# Classic-Narrow-5V-SIDE-USB-JMPR.net
KiCad netlist of a schematic drawn in EAGLE
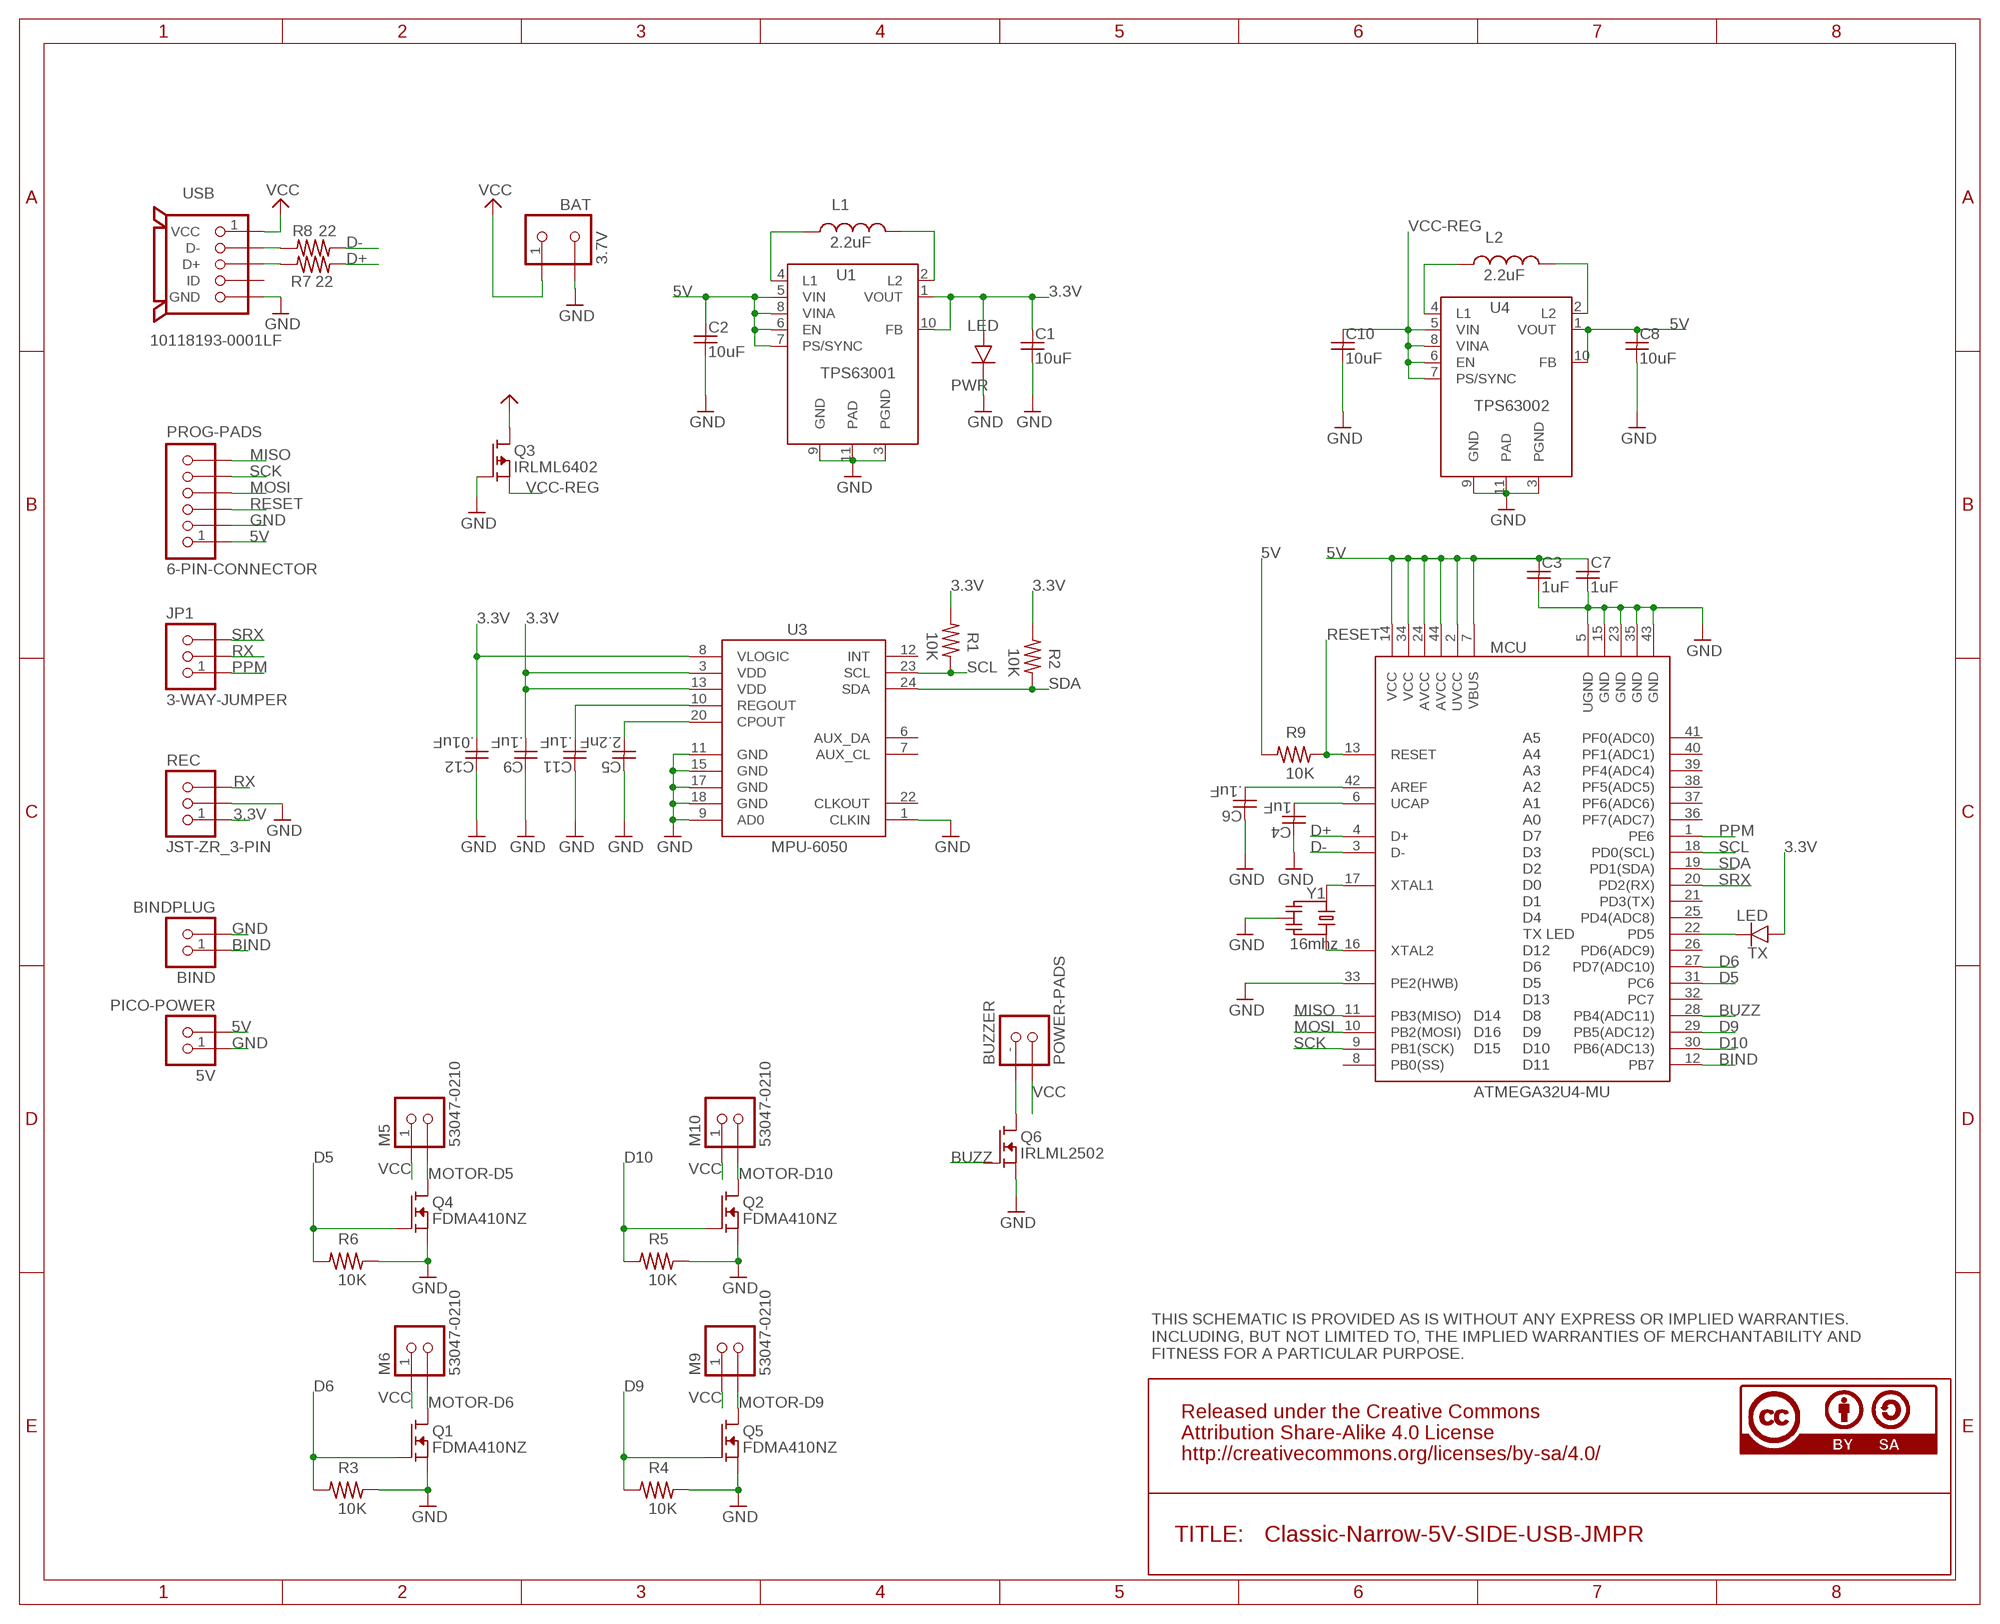
[diagram p0: schematic, sheet 1]

(export (version "E")
  (design (tool "Eeschema 10.0.6"))
  (components
    (comp (ref "5V")
      (value "PICO-POWER")
      (footprint "eagle-import:PICO_1.25_.5MM")
      (fields (field (name "MF") "Molex") (field (name "MPN") "53047-0210"))
      (libsource (lib "eagle-import") (part "PICO-POWER"))
    )
    (comp (ref "BAT")
      (value "3.7V")
      (footprint "eagle-import:S2B-PH-K-S")
      (fields (field (name "MF") "JST") (field (name "MPN") "S2B-PH-K-S"))
      (libsource (lib "eagle-import") (part "JST-PH-BAT"))
    )
    (comp (ref "BIND")
      (value "BINDPLUG")
      (footprint "eagle-import:1.27MM-PINHEADX2")
      (fields (field (name "MF") "Sullins") (field (name "MPN") "GRPB021VWVN-RC (JUMPER IS M50-1930005)"))
      (libsource (lib "eagle-import") (part "1.27MM-PINHEADX2"))
    )
    (comp (ref "BUZZER")
      (value "POWER-PADS")
      (footprint "eagle-import:POW-PADS")
      (libsource (lib "eagle-import") (part "POWER-PADS"))
    )
    (comp (ref "C1")
      (value "10uF")
      (footprint "eagle-import:YUDEN-CAP-0805")
      (fields (field (name "MF") "Taiyo Yuden") (field (name "MPN") "JMK212AB7106KG-T"))
      (libsource (lib "eagle-import") (part "CAPACITOR10UF"))
    )
    (comp (ref "C2")
      (value "10uF")
      (footprint "eagle-import:YUDEN-CAP-0805")
      (fields (field (name "MF") "Taiyo Yuden") (field (name "MPN") "JMK212AB7106KG-T"))
      (libsource (lib "eagle-import") (part "CAPACITOR10UF"))
    )
    (comp (ref "C3")
      (value "1uF")
      (footprint "eagle-import:MUR-CAP-0603")
      (fields (field (name "MF") "Murata") (field (name "MPN") "GRM188R71C105KA12D"))
      (libsource (lib "eagle-import") (part "CAPACITOR1UF"))
    )
    (comp (ref "C4")
      (value "1uF")
      (footprint "eagle-import:MUR-CAP-0603")
      (fields (field (name "MF") "Murata") (field (name "MPN") "GRM188R71C105KA12D"))
      (libsource (lib "eagle-import") (part "CAPACITOR1UF"))
    )
    (comp (ref "C5")
      (value "2.2nF")
      (footprint "eagle-import:MUR-CAP-0603")
      (fields (field (name "MF") "Murata") (field (name "MPN") "GRM188R71C222KA01D"))
      (libsource (lib "eagle-import") (part "CAPACITOR2.2NF"))
    )
    (comp (ref "C6")
      (value ".1uF")
      (footprint "eagle-import:MUR-CAP-0603")
      (fields (field (name "MF") "Murata") (field (name "MPN") "GRM188R71C104KA01D"))
      (libsource (lib "eagle-import") (part "CAPACITOR.1UF"))
    )
    (comp (ref "C7")
      (value "1uF")
      (footprint "eagle-import:MUR-CAP-0603")
      (fields (field (name "MF") "Murata") (field (name "MPN") "GRM188R71C105KA12D"))
      (libsource (lib "eagle-import") (part "CAPACITOR1UF"))
    )
    (comp (ref "C8")
      (value "10uF")
      (footprint "eagle-import:YUDEN-CAP-0805")
      (fields (field (name "MF") "Taiyo Yuden") (field (name "MPN") "JMK212AB7106KG-T"))
      (libsource (lib "eagle-import") (part "CAPACITOR10UF"))
    )
    (comp (ref "C9")
      (value ".1uF")
      (footprint "eagle-import:MUR-CAP-0603")
      (fields (field (name "MF") "Murata") (field (name "MPN") "GRM188R71C104KA01D"))
      (libsource (lib "eagle-import") (part "CAPACITOR.1UF"))
    )
    (comp (ref "C10")
      (value "10uF")
      (footprint "eagle-import:YUDEN-CAP-0805")
      (fields (field (name "MF") "Taiyo Yuden") (field (name "MPN") "JMK212AB7106KG-T"))
      (libsource (lib "eagle-import") (part "CAPACITOR10UF"))
    )
    (comp (ref "C11")
      (value ".1uF")
      (footprint "eagle-import:MUR-CAP-0603")
      (fields (field (name "MF") "Murata") (field (name "MPN") "GRM188R71C104KA01D"))
      (libsource (lib "eagle-import") (part "CAPACITOR.1UF"))
    )
    (comp (ref "C12")
      (value ".01uF")
      (footprint "eagle-import:MUR-CAP-0603")
      (fields (field (name "MF") "Murata") (field (name "MPN") "GRM188R71C103KA01D"))
      (libsource (lib "eagle-import") (part "CAPACITOR.01UF"))
    )
    (comp (ref "JP1")
      (value "3-WAY-JUMPER")
      (footprint "eagle-import:3-WAY-JUMPER")
      (libsource (lib "eagle-import") (part "3-WAY-JUMPER"))
    )
    (comp (ref "L1")
      (value "2.2uF")
      (footprint "eagle-import:NR301X")
      (fields (field (name "MF") "Taiyo Yuden") (field (name "MPN") "NR3015T2R2M"))
      (libsource (lib "eagle-import") (part "NR301X"))
    )
    (comp (ref "L2")
      (value "2.2uF")
      (footprint "eagle-import:NR301X")
      (fields (field (name "MF") "Taiyo Yuden") (field (name "MPN") "NR3015T2R2M"))
      (libsource (lib "eagle-import") (part "NR301X"))
    )
    (comp (ref "M5")
      (value "53047-0210")
      (footprint "eagle-import:PICO-53047-02")
      (fields (field (name "MF") "MOLEX"))
      (libsource (lib "eagle-import") (part "PICO-1.25-MOTOR"))
    )
    (comp (ref "M6")
      (value "53047-0210")
      (footprint "eagle-import:PICO-53047-02")
      (fields (field (name "MF") "MOLEX"))
      (libsource (lib "eagle-import") (part "PICO-1.25-MOTOR"))
    )
    (comp (ref "M9")
      (value "53047-0210")
      (footprint "eagle-import:PICO-53047-02")
      (fields (field (name "MF") "MOLEX"))
      (libsource (lib "eagle-import") (part "PICO-1.25-MOTOR"))
    )
    (comp (ref "M10")
      (value "53047-0210")
      (footprint "eagle-import:PICO-53047-02")
      (fields (field (name "MF") "MOLEX"))
      (libsource (lib "eagle-import") (part "PICO-1.25-MOTOR"))
    )
    (comp (ref "MCU")
      (value "ATMEGA32U4-MU")
      (footprint "eagle-import:QFN44-7X7")
      (fields (field (name "MF") "Atmel") (field (name "MPN") "Atmega32U4-MU"))
      (libsource (lib "eagle-import") (part "ATMEGA32U4-MU"))
    )
    (comp (ref "PROG-PADS")
      (value "6-PIN-CONNECTOR")
      (footprint "eagle-import:B6B-ZR")
      (fields (field (name "MF") "JST") (field (name "MPN") "B6B-ZR(LF)(SN)"))
      (libsource (lib "eagle-import") (part "6-PIN-CONNECTOR"))
    )
    (comp (ref "PWR")
      (value "LED")
      (footprint "eagle-import:SMD-CHIP-LED-0805")
      (fields (field (name "MF") "Kingbright") (field (name "MPN") "APHCM2012QBC/D-F01"))
      (libsource (lib "eagle-import") (part "SMD-CHIP-LED-0805"))
    )
    (comp (ref "Q1")
      (value "FDMA410NZ")
      (footprint "eagle-import:MICROFET-2X2")
      (fields (field (name "MF") "Fairchild"))
      (libsource (lib "eagle-import") (part "FDMA410NZ"))
    )
    (comp (ref "Q2")
      (value "FDMA410NZ")
      (footprint "eagle-import:MICROFET-2X2")
      (fields (field (name "MF") "Fairchild"))
      (libsource (lib "eagle-import") (part "FDMA410NZ"))
    )
    (comp (ref "Q3")
      (value "IRLML6402")
      (footprint "eagle-import:SOT-23")
      (fields (field (name "MF") "IR"))
      (libsource (lib "eagle-import") (part "MOSFET-P"))
    )
    (comp (ref "Q4")
      (value "FDMA410NZ")
      (footprint "eagle-import:MICROFET-2X2")
      (fields (field (name "MF") "Fairchild"))
      (libsource (lib "eagle-import") (part "FDMA410NZ"))
    )
    (comp (ref "Q5")
      (value "FDMA410NZ")
      (footprint "eagle-import:MICROFET-2X2")
      (fields (field (name "MF") "Fairchild"))
      (libsource (lib "eagle-import") (part "FDMA410NZ"))
    )
    (comp (ref "Q6")
      (value "IRLML2502")
      (footprint "eagle-import:SOT-23")
      (fields (field (name "MF") "IR"))
      (libsource (lib "eagle-import") (part "MOSFET-N2502"))
    )
    (comp (ref "R1")
      (value "10K")
      (footprint "eagle-import:VISH-RES-0603")
      (fields (field (name "MF") "Vishay") (field (name "MPN") "CRCW060310K0FKEAHP"))
      (libsource (lib "eagle-import") (part "RESISTOR10K"))
    )
    (comp (ref "R2")
      (value "10K")
      (footprint "eagle-import:VISH-RES-0603")
      (fields (field (name "MF") "Vishay") (field (name "MPN") "CRCW060310K0FKEAHP"))
      (libsource (lib "eagle-import") (part "RESISTOR10K"))
    )
    (comp (ref "R3")
      (value "10K")
      (footprint "eagle-import:VISH-RES-0603")
      (fields (field (name "MF") "Vishay") (field (name "MPN") "CRCW060310K0FKEAHP"))
      (libsource (lib "eagle-import") (part "RESISTOR10K"))
    )
    (comp (ref "R4")
      (value "10K")
      (footprint "eagle-import:VISH-RES-0603")
      (fields (field (name "MF") "Vishay") (field (name "MPN") "CRCW060310K0FKEAHP"))
      (libsource (lib "eagle-import") (part "RESISTOR10K"))
    )
    (comp (ref "R5")
      (value "10K")
      (footprint "eagle-import:VISH-RES-0603")
      (fields (field (name "MF") "Vishay") (field (name "MPN") "CRCW060310K0FKEAHP"))
      (libsource (lib "eagle-import") (part "RESISTOR10K"))
    )
    (comp (ref "R6")
      (value "10K")
      (footprint "eagle-import:VISH-RES-0603")
      (fields (field (name "MF") "Vishay") (field (name "MPN") "CRCW060310K0FKEAHP"))
      (libsource (lib "eagle-import") (part "RESISTOR10K"))
    )
    (comp (ref "R7")
      (value "22")
      (footprint "eagle-import:VISH-RES-0603")
      (fields (field (name "MF") "Vishay") (field (name "MPN") "CRCW060322R0FKEAHP"))
      (libsource (lib "eagle-import") (part "RESISTOR22"))
    )
    (comp (ref "R8")
      (value "22")
      (footprint "eagle-import:VISH-RES-0603")
      (fields (field (name "MF") "Vishay") (field (name "MPN") "CRCW060322R0FKEAHP"))
      (libsource (lib "eagle-import") (part "RESISTOR22"))
    )
    (comp (ref "R9")
      (value "10K")
      (footprint "eagle-import:VISH-RES-0603")
      (fields (field (name "MF") "Vishay") (field (name "MPN") "CRCW060310K0FKEAHP"))
      (libsource (lib "eagle-import") (part "RESISTOR10K"))
    )
    (comp (ref "REC")
      (value "JST-ZR_3-PIN")
      (footprint "eagle-import:S3B-ZR")
      (fields (field (name "MF") "JST") (field (name "MPN") "S3B-ZR"))
      (libsource (lib "eagle-import") (part "JST-ZR_3-PIN"))
    )
    (comp (ref "TX")
      (value "LED")
      (footprint "eagle-import:SMD-CHIP-LED-0805")
      (fields (field (name "MF") "Kingbright") (field (name "MPN") "APHCM2012QBC/D-F01"))
      (libsource (lib "eagle-import") (part "SMD-CHIP-LED-0805"))
    )
    (comp (ref "U1")
      (value "TPS63001")
      (footprint "eagle-import:VSON-N10")
      (fields (field (name "MF") "TI") (field (name "MPN") "TPS63001DRCR"))
      (libsource (lib "eagle-import") (part "TPS630XX-TPS63001"))
    )
    (comp (ref "U3")
      (value "MPU-6050")
      (footprint "eagle-import:QFN24-4X4")
      (fields (field (name "MF") "Invensense"))
      (libsource (lib "eagle-import") (part "MPU-6050"))
    )
    (comp (ref "U4")
      (value "TPS63002")
      (footprint "eagle-import:VSON-N10")
      (fields (field (name "MF") "TI") (field (name "MPN") "TPS63002DRCR"))
      (libsource (lib "eagle-import") (part "TPS630XX-TPS63002"))
    )
    (comp (ref "USB")
      (value "10118193-0001LF")
      (footprint "eagle-import:10118193-0001LF")
      (fields (field (name "MF") "FCI"))
      (libsource (lib "eagle-import") (part "USB-MICRO-B-FCI"))
    )
    (comp (ref "Y1")
      (value "16mhz")
      (footprint "eagle-import:RESONATOR_16")
      (fields (field (name "MF") "Murata") (field (name "MPN") "CSTCE16M0V53-R0"))
      (libsource (lib "eagle-import") (part "RESONATOR16MHZ"))
    )
  )
  (nets
    (net (code "1") (name "/3.3V") (class "Default")
      (node (ref "C1") (pin "1") (pinfunction "1_1") (pintype "passive"))
      (node (ref "C12") (pin "2") (pinfunction "2_2") (pintype "passive"))
      (node (ref "C9") (pin "2") (pinfunction "2_2") (pintype "passive"))
      (node (ref "PWR") (pin "A") (pinfunction "A_A") (pintype "passive"))
      (node (ref "R1") (pin "2") (pinfunction "2_2") (pintype "passive"))
      (node (ref "R2") (pin "2") (pinfunction "2_2") (pintype "passive"))
      (node (ref "REC") (pin "1") (pinfunction "1_1") (pintype "bidirectional"))
      (node (ref "TX") (pin "A") (pinfunction "A_A") (pintype "passive"))
      (node (ref "U1") (pin "1") (pinfunction "VOUT_1") (pintype "bidirectional"))
      (node (ref "U1") (pin "10") (pinfunction "FB_10") (pintype "bidirectional"))
      (node (ref "U3") (pin "13") (pinfunction "VDD_13") (pintype "bidirectional"))
      (node (ref "U3") (pin "3") (pinfunction "VDD_3") (pintype "bidirectional"))
      (node (ref "U3") (pin "8") (pinfunction "VLOGIC_8") (pintype "bidirectional"))
    )
    (net (code "2") (name "/5V") (class "Default")
      (node (ref "5V") (pin "2") (pinfunction "2_2") (pintype "passive"))
      (node (ref "C2") (pin "1") (pinfunction "1_1") (pintype "passive"))
      (node (ref "C3") (pin "1") (pinfunction "1_1") (pintype "passive"))
      (node (ref "C7") (pin "1") (pinfunction "1_1") (pintype "passive"))
      (node (ref "C8") (pin "1") (pinfunction "1_1") (pintype "passive"))
      (node (ref "MCU") (pin "14") (pinfunction "VCC_14") (pintype "bidirectional"))
      (node (ref "MCU") (pin "2") (pinfunction "UVCC_2") (pintype "bidirectional"))
      (node (ref "MCU") (pin "24") (pinfunction "AVCC_24") (pintype "bidirectional"))
      (node (ref "MCU") (pin "34") (pinfunction "VCC_34") (pintype "bidirectional"))
      (node (ref "MCU") (pin "44") (pinfunction "AVCC_44") (pintype "bidirectional"))
      (node (ref "MCU") (pin "7") (pinfunction "VBUS_7") (pintype "bidirectional"))
      (node (ref "PROG-PADS") (pin "1") (pinfunction "1_1") (pintype "bidirectional"))
      (node (ref "R9") (pin "2") (pinfunction "2_2") (pintype "passive"))
      (node (ref "U1") (pin "5") (pinfunction "VIN_5") (pintype "bidirectional"))
      (node (ref "U1") (pin "6") (pinfunction "EN_6") (pintype "bidirectional"))
      (node (ref "U1") (pin "7") (pinfunction "PS/SYNC_7") (pintype "bidirectional"))
      (node (ref "U1") (pin "8") (pinfunction "VINA_8") (pintype "bidirectional"))
      (node (ref "U4") (pin "1") (pinfunction "VOUT_1") (pintype "bidirectional"))
      (node (ref "U4") (pin "10") (pinfunction "FB_10") (pintype "bidirectional"))
    )
    (net (code "3") (name "/BIND") (class "Default")
      (node (ref "BIND") (pin "1") (pinfunction "1_1") (pintype "passive"))
      (node (ref "MCU") (pin "12") (pinfunction "PB7_12") (pintype "bidirectional"))
    )
    (net (code "4") (name "/BUZZ") (class "Default")
      (node (ref "MCU") (pin "28") (pinfunction "PB4(ADC11)_28") (pintype "bidirectional"))
      (node (ref "Q6") (pin "1") (pinfunction "G_1") (pintype "bidirectional"))
    )
    (net (code "5") (name "/D+") (class "Default")
      (node (ref "MCU") (pin "4") (pinfunction "D+_4") (pintype "bidirectional"))
      (node (ref "R7") (pin "1") (pinfunction "1_1") (pintype "passive"))
    )
    (net (code "6") (name "/D-") (class "Default")
      (node (ref "MCU") (pin "3") (pinfunction "D-_3") (pintype "bidirectional"))
      (node (ref "R8") (pin "1") (pinfunction "1_1") (pintype "passive"))
    )
    (net (code "7") (name "/D5") (class "Default")
      (node (ref "MCU") (pin "31") (pinfunction "PC6_31") (pintype "bidirectional"))
      (node (ref "Q4") (pin "G") (pinfunction "G_G") (pintype "bidirectional"))
      (node (ref "R6") (pin "2") (pinfunction "2_2") (pintype "passive"))
    )
    (net (code "8") (name "/D6") (class "Default")
      (node (ref "MCU") (pin "27") (pinfunction "PD7(ADC10)_27") (pintype "bidirectional"))
      (node (ref "Q1") (pin "G") (pinfunction "G_G") (pintype "bidirectional"))
      (node (ref "R3") (pin "2") (pinfunction "2_2") (pintype "passive"))
    )
    (net (code "9") (name "/D9") (class "Default")
      (node (ref "MCU") (pin "29") (pinfunction "PB5(ADC12)_29") (pintype "bidirectional"))
      (node (ref "Q5") (pin "G") (pinfunction "G_G") (pintype "bidirectional"))
      (node (ref "R4") (pin "2") (pinfunction "2_2") (pintype "passive"))
    )
    (net (code "10") (name "/D10") (class "Default")
      (node (ref "MCU") (pin "30") (pinfunction "PB6(ADC13)_30") (pintype "bidirectional"))
      (node (ref "Q2") (pin "G") (pinfunction "G_G") (pintype "bidirectional"))
      (node (ref "R5") (pin "2") (pinfunction "2_2") (pintype "passive"))
    )
    (net (code "11") (name "/MISO") (class "Default")
      (node (ref "MCU") (pin "11") (pinfunction "PB3(MISO)_11") (pintype "bidirectional"))
      (node (ref "PROG-PADS") (pin "6") (pinfunction "6_6") (pintype "bidirectional"))
    )
    (net (code "12") (name "/MOSI") (class "Default")
      (node (ref "MCU") (pin "10") (pinfunction "PB2(MOSI)_10") (pintype "bidirectional"))
      (node (ref "PROG-PADS") (pin "4") (pinfunction "4_4") (pintype "bidirectional"))
    )
    (net (code "13") (name "/MOTOR-D5") (class "Default")
      (node (ref "M5") (pin "2") (pinfunction "2_2") (pintype "passive"))
      (node (ref "Q4") (pin "D") (pinfunction "D_D") (pintype "bidirectional"))
      (node (ref "Q4") (pin "D1") (pinfunction "D_D1") (pintype "bidirectional"))
      (node (ref "Q4") (pin "D2") (pinfunction "D_D2") (pintype "bidirectional"))
      (node (ref "Q4") (pin "D3") (pinfunction "D_D3") (pintype "bidirectional"))
      (node (ref "Q4") (pin "D4") (pinfunction "D_D4") (pintype "bidirectional"))
    )
    (net (code "14") (name "/MOTOR-D6") (class "Default")
      (node (ref "M6") (pin "2") (pinfunction "2_2") (pintype "passive"))
      (node (ref "Q1") (pin "D") (pinfunction "D_D") (pintype "bidirectional"))
      (node (ref "Q1") (pin "D1") (pinfunction "D_D1") (pintype "bidirectional"))
      (node (ref "Q1") (pin "D2") (pinfunction "D_D2") (pintype "bidirectional"))
      (node (ref "Q1") (pin "D3") (pinfunction "D_D3") (pintype "bidirectional"))
      (node (ref "Q1") (pin "D4") (pinfunction "D_D4") (pintype "bidirectional"))
    )
    (net (code "15") (name "/MOTOR-D9") (class "Default")
      (node (ref "M9") (pin "2") (pinfunction "2_2") (pintype "passive"))
      (node (ref "Q5") (pin "D") (pinfunction "D_D") (pintype "bidirectional"))
      (node (ref "Q5") (pin "D1") (pinfunction "D_D1") (pintype "bidirectional"))
      (node (ref "Q5") (pin "D2") (pinfunction "D_D2") (pintype "bidirectional"))
      (node (ref "Q5") (pin "D3") (pinfunction "D_D3") (pintype "bidirectional"))
      (node (ref "Q5") (pin "D4") (pinfunction "D_D4") (pintype "bidirectional"))
    )
    (net (code "16") (name "/MOTOR-D10") (class "Default")
      (node (ref "M10") (pin "2") (pinfunction "2_2") (pintype "passive"))
      (node (ref "Q2") (pin "D") (pinfunction "D_D") (pintype "bidirectional"))
      (node (ref "Q2") (pin "D1") (pinfunction "D_D1") (pintype "bidirectional"))
      (node (ref "Q2") (pin "D2") (pinfunction "D_D2") (pintype "bidirectional"))
      (node (ref "Q2") (pin "D3") (pinfunction "D_D3") (pintype "bidirectional"))
      (node (ref "Q2") (pin "D4") (pinfunction "D_D4") (pintype "bidirectional"))
    )
    (net (code "17") (name "/PPM") (class "Default")
      (node (ref "JP1") (pin "1") (pinfunction "1_1") (pintype "bidirectional"))
      (node (ref "MCU") (pin "1") (pinfunction "PE6_1") (pintype "bidirectional"))
    )
    (net (code "18") (name "/RESET") (class "Default")
      (node (ref "MCU") (pin "13") (pinfunction "RESET_13") (pintype "bidirectional"))
      (node (ref "PROG-PADS") (pin "3") (pinfunction "3_3") (pintype "bidirectional"))
      (node (ref "R9") (pin "1") (pinfunction "1_1") (pintype "passive"))
    )
    (net (code "19") (name "/RX") (class "Default")
      (node (ref "JP1") (pin "2") (pinfunction "2_2") (pintype "bidirectional"))
      (node (ref "REC") (pin "3") (pinfunction "3_3") (pintype "bidirectional"))
    )
    (net (code "20") (name "/SCK") (class "Default")
      (node (ref "MCU") (pin "9") (pinfunction "PB1(SCK)_9") (pintype "bidirectional"))
      (node (ref "PROG-PADS") (pin "5") (pinfunction "5_5") (pintype "bidirectional"))
    )
    (net (code "21") (name "/SCL") (class "Default")
      (node (ref "MCU") (pin "18") (pinfunction "PD0(SCL)_18") (pintype "bidirectional"))
      (node (ref "R1") (pin "1") (pinfunction "1_1") (pintype "passive"))
      (node (ref "U3") (pin "23") (pinfunction "SCL_23") (pintype "bidirectional"))
    )
    (net (code "22") (name "/SDA") (class "Default")
      (node (ref "MCU") (pin "19") (pinfunction "PD1(SDA)_19") (pintype "bidirectional"))
      (node (ref "R2") (pin "1") (pinfunction "1_1") (pintype "passive"))
      (node (ref "U3") (pin "24") (pinfunction "SDA_24") (pintype "bidirectional"))
    )
    (net (code "23") (name "/SRX") (class "Default")
      (node (ref "JP1") (pin "3") (pinfunction "3_3") (pintype "bidirectional"))
      (node (ref "MCU") (pin "20") (pinfunction "PD2(RX)_20") (pintype "bidirectional"))
    )
    (net (code "24") (name "/VCC-REG") (class "Default")
      (node (ref "C10") (pin "1") (pinfunction "1_1") (pintype "passive"))
      (node (ref "Q3") (pin "2") (pinfunction "S_2") (pintype "bidirectional"))
      (node (ref "U4") (pin "5") (pinfunction "VIN_5") (pintype "bidirectional"))
      (node (ref "U4") (pin "6") (pinfunction "EN_6") (pintype "bidirectional"))
      (node (ref "U4") (pin "7") (pinfunction "PS/SYNC_7") (pintype "bidirectional"))
      (node (ref "U4") (pin "8") (pinfunction "VINA_8") (pintype "bidirectional"))
    )
    (net (code "25") (name "GND") (class "Default")
      (node (ref "5V") (pin "1") (pinfunction "1_1") (pintype "passive"))
      (node (ref "BAT") (pin "2") (pinfunction "2_2") (pintype "bidirectional"))
      (node (ref "BIND") (pin "2") (pinfunction "2_2") (pintype "passive"))
      (node (ref "C1") (pin "2") (pinfunction "2_2") (pintype "passive"))
      (node (ref "C10") (pin "2") (pinfunction "2_2") (pintype "passive"))
      (node (ref "C11") (pin "1") (pinfunction "1_1") (pintype "passive"))
      (node (ref "C12") (pin "1") (pinfunction "1_1") (pintype "passive"))
      (node (ref "C2") (pin "2") (pinfunction "2_2") (pintype "passive"))
      (node (ref "C3") (pin "2") (pinfunction "2_2") (pintype "passive"))
      (node (ref "C4") (pin "1") (pinfunction "1_1") (pintype "passive"))
      (node (ref "C5") (pin "1") (pinfunction "1_1") (pintype "passive"))
      (node (ref "C6") (pin "1") (pinfunction "1_1") (pintype "passive"))
      (node (ref "C7") (pin "2") (pinfunction "2_2") (pintype "passive"))
      (node (ref "C8") (pin "2") (pinfunction "2_2") (pintype "passive"))
      (node (ref "C9") (pin "1") (pinfunction "1_1") (pintype "passive"))
      (node (ref "MCU") (pin "15") (pinfunction "GND_15") (pintype "bidirectional"))
      (node (ref "MCU") (pin "23") (pinfunction "GND_23") (pintype "bidirectional"))
      (node (ref "MCU") (pin "33") (pinfunction "PE2(HWB)_33") (pintype "bidirectional"))
      (node (ref "MCU") (pin "35") (pinfunction "GND_35") (pintype "bidirectional"))
      (node (ref "MCU") (pin "43") (pinfunction "GND_43") (pintype "bidirectional"))
      (node (ref "MCU") (pin "5") (pinfunction "UGND_5") (pintype "bidirectional"))
      (node (ref "PROG-PADS") (pin "2") (pinfunction "2_2") (pintype "bidirectional"))
      (node (ref "PWR") (pin "C") (pinfunction "C_C") (pintype "passive"))
      (node (ref "Q1") (pin "S") (pinfunction "S_S") (pintype "bidirectional"))
      (node (ref "Q1") (pin "S1") (pinfunction "S_S1") (pintype "bidirectional"))
      (node (ref "Q2") (pin "S") (pinfunction "S_S") (pintype "bidirectional"))
      (node (ref "Q2") (pin "S1") (pinfunction "S_S1") (pintype "bidirectional"))
      (node (ref "Q3") (pin "1") (pinfunction "G_1") (pintype "bidirectional"))
      (node (ref "Q4") (pin "S") (pinfunction "S_S") (pintype "bidirectional"))
      (node (ref "Q4") (pin "S1") (pinfunction "S_S1") (pintype "bidirectional"))
      (node (ref "Q5") (pin "S") (pinfunction "S_S") (pintype "bidirectional"))
      (node (ref "Q5") (pin "S1") (pinfunction "S_S1") (pintype "bidirectional"))
      (node (ref "Q6") (pin "2") (pinfunction "S_2") (pintype "bidirectional"))
      (node (ref "R3") (pin "1") (pinfunction "1_1") (pintype "passive"))
      (node (ref "R4") (pin "1") (pinfunction "1_1") (pintype "passive"))
      (node (ref "R5") (pin "1") (pinfunction "1_1") (pintype "passive"))
      (node (ref "R6") (pin "1") (pinfunction "1_1") (pintype "passive"))
      (node (ref "REC") (pin "2") (pinfunction "2_2") (pintype "bidirectional"))
      (node (ref "U1") (pin "11") (pinfunction "PAD_11") (pintype "bidirectional"))
      (node (ref "U1") (pin "3") (pinfunction "PGND_3") (pintype "bidirectional"))
      (node (ref "U1") (pin "9") (pinfunction "GND_9") (pintype "bidirectional"))
      (node (ref "U3") (pin "1") (pinfunction "CLKIN_1") (pintype "bidirectional"))
      (node (ref "U3") (pin "11") (pinfunction "GND_11") (pintype "bidirectional"))
      (node (ref "U3") (pin "15") (pinfunction "GND_15") (pintype "bidirectional"))
      (node (ref "U3") (pin "17") (pinfunction "GND_17") (pintype "bidirectional"))
      (node (ref "U3") (pin "18") (pinfunction "GND_18") (pintype "bidirectional"))
      (node (ref "U3") (pin "9") (pinfunction "AD0_9") (pintype "bidirectional"))
      (node (ref "U4") (pin "11") (pinfunction "PAD_11") (pintype "bidirectional"))
      (node (ref "U4") (pin "3") (pinfunction "PGND_3") (pintype "bidirectional"))
      (node (ref "U4") (pin "9") (pinfunction "GND_9") (pintype "bidirectional"))
      (node (ref "USB") (pin "5") (pinfunction "GND_5") (pintype "passive"))
      (node (ref "USB") (pin "GND") (pinfunction "GND_GND") (pintype "passive"))
      (node (ref "USB") (pin "GND2") (pinfunction "GND_GND2") (pintype "passive"))
      (node (ref "USB") (pin "HOLE1") (pinfunction "GND_HOLE1") (pintype "passive"))
      (node (ref "USB") (pin "HOLE2") (pinfunction "GND_HOLE2") (pintype "passive"))
      (node (ref "Y1") (pin "2") (pinfunction "2_2") (pintype "passive"))
    )
    (net (code "26") (name "Net-(BUZZER-1)") (class "Default")
      (node (ref "BUZZER") (pin "-") (pinfunction "1_-") (pintype "passive"))
      (node (ref "Q6") (pin "3") (pinfunction "D_3") (pintype "bidirectional"))
    )
    (net (code "27") (name "Net-(MCU-AREF)") (class "Default")
      (node (ref "C6") (pin "2") (pinfunction "2_2") (pintype "passive"))
      (node (ref "MCU") (pin "42") (pinfunction "AREF_42") (pintype "bidirectional"))
    )
    (net (code "28") (name "Net-(MCU-PD5)") (class "Default")
      (node (ref "MCU") (pin "22") (pinfunction "PD5_22") (pintype "bidirectional"))
      (node (ref "TX") (pin "C") (pinfunction "C_C") (pintype "passive"))
    )
    (net (code "29") (name "Net-(MCU-UCAP)") (class "Default")
      (node (ref "C4") (pin "2") (pinfunction "2_2") (pintype "passive"))
      (node (ref "MCU") (pin "6") (pinfunction "UCAP_6") (pintype "bidirectional"))
    )
    (net (code "30") (name "Net-(MCU-XTAL1)") (class "Default")
      (node (ref "MCU") (pin "17") (pinfunction "XTAL1_17") (pintype "bidirectional"))
      (node (ref "Y1") (pin "1") (pinfunction "1_1") (pintype "passive"))
    )
    (net (code "31") (name "Net-(MCU-XTAL2)") (class "Default")
      (node (ref "MCU") (pin "16") (pinfunction "XTAL2_16") (pintype "bidirectional"))
      (node (ref "Y1") (pin "3") (pinfunction "3_3") (pintype "passive"))
    )
    (net (code "32") (name "Net-(U1-L1)") (class "Default")
      (node (ref "L1") (pin "1") (pinfunction "1_1") (pintype "passive"))
      (node (ref "U1") (pin "4") (pinfunction "L1_4") (pintype "bidirectional"))
    )
    (net (code "33") (name "Net-(U1-L2)") (class "Default")
      (node (ref "L1") (pin "2") (pinfunction "2_2") (pintype "passive"))
      (node (ref "U1") (pin "2") (pinfunction "L2_2") (pintype "bidirectional"))
    )
    (net (code "34") (name "Net-(U3-CPOUT)") (class "Default")
      (node (ref "C5") (pin "2") (pinfunction "2_2") (pintype "passive"))
      (node (ref "U3") (pin "20") (pinfunction "CPOUT_20") (pintype "bidirectional"))
    )
    (net (code "35") (name "Net-(U3-REGOUT)") (class "Default")
      (node (ref "C11") (pin "2") (pinfunction "2_2") (pintype "passive"))
      (node (ref "U3") (pin "10") (pinfunction "REGOUT_10") (pintype "bidirectional"))
    )
    (net (code "36") (name "Net-(U4-L1)") (class "Default")
      (node (ref "L2") (pin "1") (pinfunction "1_1") (pintype "passive"))
      (node (ref "U4") (pin "4") (pinfunction "L1_4") (pintype "bidirectional"))
    )
    (net (code "37") (name "Net-(U4-L2)") (class "Default")
      (node (ref "L2") (pin "2") (pinfunction "2_2") (pintype "passive"))
      (node (ref "U4") (pin "2") (pinfunction "L2_2") (pintype "bidirectional"))
    )
    (net (code "38") (name "Net-(USB-D+)") (class "Default")
      (node (ref "R7") (pin "2") (pinfunction "2_2") (pintype "passive"))
      (node (ref "USB") (pin "3") (pinfunction "D+_3") (pintype "passive"))
    )
    (net (code "39") (name "Net-(USB-D-)") (class "Default")
      (node (ref "R8") (pin "2") (pinfunction "2_2") (pintype "passive"))
      (node (ref "USB") (pin "2") (pinfunction "D-_2") (pintype "passive"))
    )
    (net (code "40") (name "VCC") (class "Default")
      (node (ref "BAT") (pin "1") (pinfunction "1_1") (pintype "bidirectional"))
      (node (ref "BUZZER") (pin "+") (pinfunction "2_+") (pintype "passive"))
      (node (ref "M10") (pin "1") (pinfunction "1_1") (pintype "passive"))
      (node (ref "M5") (pin "1") (pinfunction "1_1") (pintype "passive"))
      (node (ref "M6") (pin "1") (pinfunction "1_1") (pintype "passive"))
      (node (ref "M9") (pin "1") (pinfunction "1_1") (pintype "passive"))
      (node (ref "Q3") (pin "3") (pinfunction "D_3") (pintype "bidirectional"))
      (node (ref "USB") (pin "1") (pinfunction "VCC_1") (pintype "passive"))
    )
    (net (code "41") (name "unconnected-(MCU-PB0(SS)-Pad8)") (class "Default")
      (node (ref "MCU") (pin "8") (pinfunction "PB0(SS)_8") (pintype "bidirectional"))
    )
    (net (code "42") (name "unconnected-(MCU-PC7-Pad32)") (class "Default")
      (node (ref "MCU") (pin "32") (pinfunction "PC7_32") (pintype "bidirectional"))
    )
    (net (code "43") (name "unconnected-(MCU-PD3(TX)-Pad21)") (class "Default")
      (node (ref "MCU") (pin "21") (pinfunction "PD3(TX)_21") (pintype "bidirectional"))
    )
    (net (code "44") (name "unconnected-(MCU-PD4(ADC8)-Pad25)") (class "Default")
      (node (ref "MCU") (pin "25") (pinfunction "PD4(ADC8)_25") (pintype "bidirectional"))
    )
    (net (code "45") (name "unconnected-(MCU-PD6(ADC9)-Pad26)") (class "Default")
      (node (ref "MCU") (pin "26") (pinfunction "PD6(ADC9)_26") (pintype "bidirectional"))
    )
    (net (code "46") (name "unconnected-(MCU-PF0(ADC0)-Pad41)") (class "Default")
      (node (ref "MCU") (pin "41") (pinfunction "PF0(ADC0)_41") (pintype "bidirectional"))
    )
    (net (code "47") (name "unconnected-(MCU-PF1(ADC1)-Pad40)") (class "Default")
      (node (ref "MCU") (pin "40") (pinfunction "PF1(ADC1)_40") (pintype "bidirectional"))
    )
    (net (code "48") (name "unconnected-(MCU-PF4(ADC4)-Pad39)") (class "Default")
      (node (ref "MCU") (pin "39") (pinfunction "PF4(ADC4)_39") (pintype "bidirectional"))
    )
    (net (code "49") (name "unconnected-(MCU-PF5(ADC5)-Pad38)") (class "Default")
      (node (ref "MCU") (pin "38") (pinfunction "PF5(ADC5)_38") (pintype "bidirectional"))
    )
    (net (code "50") (name "unconnected-(MCU-PF6(ADC6)-Pad37)") (class "Default")
      (node (ref "MCU") (pin "37") (pinfunction "PF6(ADC6)_37") (pintype "bidirectional"))
    )
    (net (code "51") (name "unconnected-(MCU-PF7(ADC7)-Pad36)") (class "Default")
      (node (ref "MCU") (pin "36") (pinfunction "PF7(ADC7)_36") (pintype "bidirectional"))
    )
    (net (code "52") (name "unconnected-(U3-AUX_CL-Pad7)") (class "Default")
      (node (ref "U3") (pin "7") (pinfunction "AUX_CL_7") (pintype "bidirectional"))
    )
    (net (code "53") (name "unconnected-(U3-AUX_DA-Pad6)") (class "Default")
      (node (ref "U3") (pin "6") (pinfunction "AUX_DA_6") (pintype "bidirectional"))
    )
    (net (code "54") (name "unconnected-(U3-CLKOUT-Pad22)") (class "Default")
      (node (ref "U3") (pin "22") (pinfunction "CLKOUT_22") (pintype "bidirectional"))
    )
    (net (code "55") (name "unconnected-(U3-INT-Pad12)") (class "Default")
      (node (ref "U3") (pin "12") (pinfunction "INT_12") (pintype "bidirectional"))
    )
    (net (code "56") (name "unconnected-(USB-ID-Pad4)") (class "Default")
      (node (ref "USB") (pin "4") (pinfunction "ID_4") (pintype "passive"))
    )
  )
)
